# mkr1000.net
KiCad netlist of a schematic drawn in EAGLE
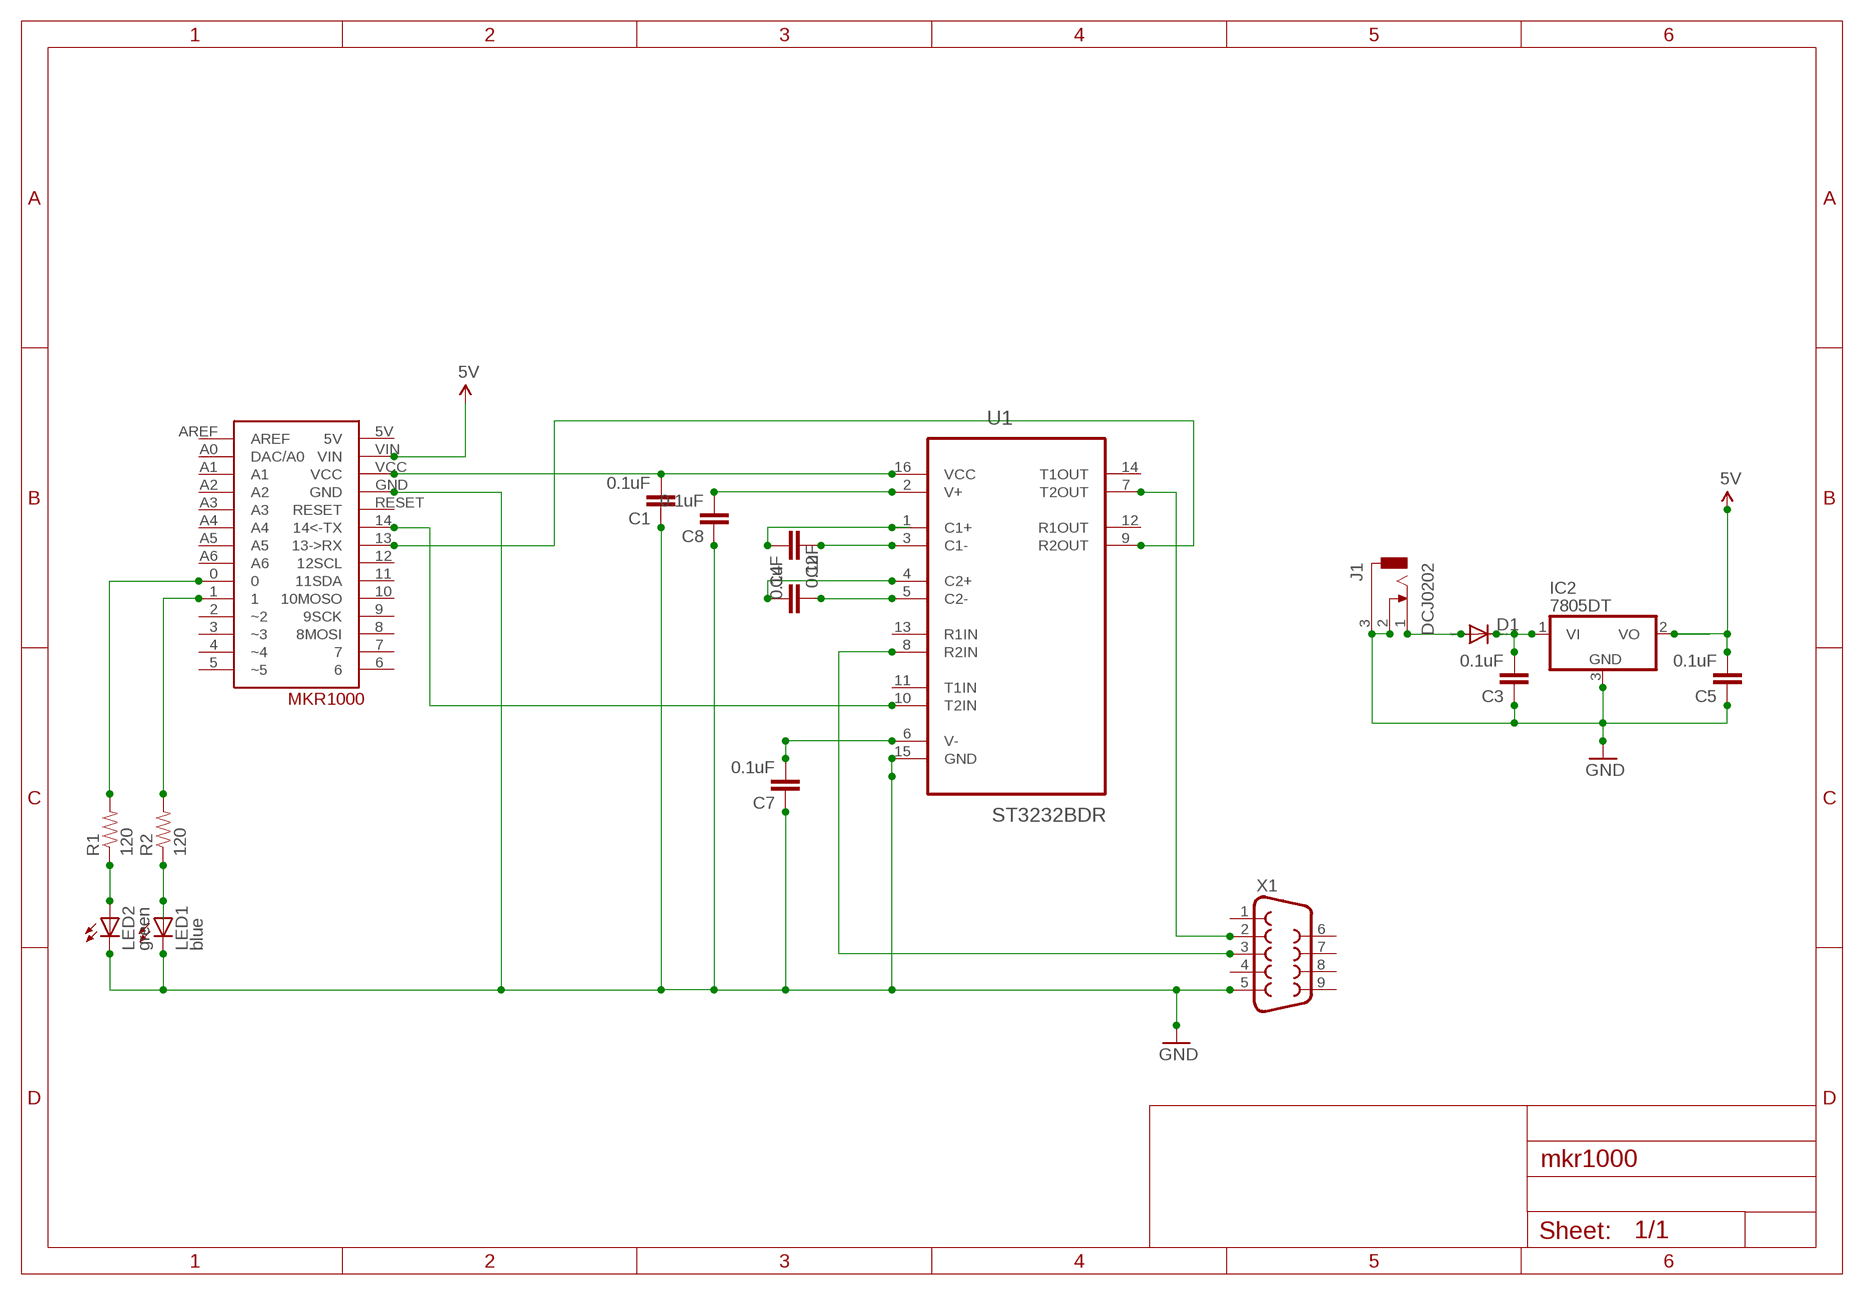
[diagram p0: schematic, sheet 1]

(export (version "E")
  (design (tool "Eeschema 10.0.6"))
  (components
    (comp (ref "C1")
      (value "0.1uF")
      (footprint "eagle-import:0603-CAP")
      (libsource (lib "eagle-import") (part "0.1UF-25V(+80/-20%)(0603)"))
    )
    (comp (ref "C2")
      (value "0.1uF")
      (footprint "eagle-import:0603-CAP")
      (libsource (lib "eagle-import") (part "0.1UF-25V(+80/-20%)(0603)"))
    )
    (comp (ref "C3")
      (value "0.1uF")
      (footprint "eagle-import:0603-CAP")
      (libsource (lib "eagle-import") (part "0.1UF-25V(+80/-20%)(0603)"))
    )
    (comp (ref "C4")
      (value "0.1uF")
      (footprint "eagle-import:0603-CAP")
      (libsource (lib "eagle-import") (part "0.1UF-25V(+80/-20%)(0603)"))
    )
    (comp (ref "C5")
      (value "0.1uF")
      (footprint "eagle-import:0603-CAP")
      (libsource (lib "eagle-import") (part "0.1UF-25V(+80/-20%)(0603)"))
    )
    (comp (ref "C7")
      (value "0.1uF")
      (footprint "eagle-import:0603-CAP")
      (libsource (lib "eagle-import") (part "0.1UF-25V(+80/-20%)(0603)"))
    )
    (comp (ref "C8")
      (value "0.1uF")
      (footprint "eagle-import:0603-CAP")
      (libsource (lib "eagle-import") (part "0.1UF-25V(+80/-20%)(0603)"))
    )
    (comp (ref "D1")
      (value "DIODE-SMB")
      (footprint "eagle-import:SMB")
      (libsource (lib "eagle-import") (part "DIODE-SMB"))
    )
    (comp (ref "IC2")
      (value "7805DT")
      (footprint "eagle-import:TO252")
      (libsource (lib "eagle-import") (part "78DT05"))
    )
    (comp (ref "J1")
      (value "DCJ0202")
      (footprint "eagle-import:DCJ0202")
      (libsource (lib "eagle-import") (part "DCJ0202"))
    )
    (comp (ref "LED1")
      (value "blue")
      (footprint "eagle-import:SML0805")
      (libsource (lib "eagle-import") (part "LEDSML0805"))
    )
    (comp (ref "LED2")
      (value "green")
      (footprint "eagle-import:SML0805")
      (libsource (lib "eagle-import") (part "LEDSML0805"))
    )
    (comp (ref "MKR1000")
      (value "MKR1000")
      (footprint "eagle-import:MKR1000")
      (libsource (lib "eagle-import") (part "MKR1000"))
    )
    (comp (ref "R1")
      (value "120")
      (footprint "eagle-import:0805")
      (libsource (lib "eagle-import") (part "RESISTOR0805-RES"))
    )
    (comp (ref "R2")
      (value "120")
      (footprint "eagle-import:0805")
      (libsource (lib "eagle-import") (part "RESISTOR0805-RES"))
    )
    (comp (ref "U1")
      (value "ST3232BDR")
      (footprint "eagle-import:SOIC127P600X175-16N")
      (libsource (lib "eagle-import") (part "ST3232BDR"))
    )
    (comp (ref "X1")
      (value "DB9FEMALE")
      (footprint "eagle-import:DB9")
      (libsource (lib "eagle-import") (part "DB9FEMALE"))
    )
  )
  (nets
    (net (code "1") (name "5V") (class "Default")
      (node (ref "C5") (pin "2") (pinfunction "2_2") (pintype "passive"))
      (node (ref "IC2") (pin "2") (pinfunction "VO_2") (pintype "passive"))
      (node (ref "MKR1000") (pin "VIN") (pinfunction "VIN_VIN") (pintype "bidirectional"))
    )
    (net (code "2") (name "GND") (class "Default")
      (node (ref "C1") (pin "1") (pinfunction "1_1") (pintype "passive"))
      (node (ref "C3") (pin "1") (pinfunction "1_1") (pintype "passive"))
      (node (ref "C5") (pin "1") (pinfunction "1_1") (pintype "passive"))
      (node (ref "C7") (pin "1") (pinfunction "1_1") (pintype "passive"))
      (node (ref "C8") (pin "1") (pinfunction "1_1") (pintype "passive"))
      (node (ref "IC2") (pin "3") (pinfunction "GND_3") (pintype "passive"))
      (node (ref "J1") (pin "2") (pinfunction "2_2") (pintype "passive"))
      (node (ref "J1") (pin "3") (pinfunction "1_3") (pintype "passive"))
      (node (ref "LED1") (pin "C") (pinfunction "C_C") (pintype "passive"))
      (node (ref "LED2") (pin "C") (pinfunction "C_C") (pintype "passive"))
      (node (ref "MKR1000") (pin "GND") (pinfunction "GND_GND") (pintype "bidirectional"))
      (node (ref "U1") (pin "15") (pinfunction "GND_15") (pintype "passive"))
      (node (ref "X1") (pin "5") (pinfunction "5_5") (pintype "passive"))
    )
    (net (code "3") (name "Net-(IC2-VI)") (class "Default")
      (node (ref "C3") (pin "2") (pinfunction "2_2") (pintype "passive"))
      (node (ref "D1") (pin "C") (pinfunction "C_C") (pintype "passive"))
      (node (ref "IC2") (pin "1") (pinfunction "VI_1") (pintype "input"))
    )
    (net (code "4") (name "Net-(J1-3)") (class "Default")
      (node (ref "D1") (pin "A") (pinfunction "A_A") (pintype "passive"))
      (node (ref "J1") (pin "1") (pinfunction "3_1") (pintype "passive"))
    )
    (net (code "5") (name "Net-(LED1-PadA)") (class "Default")
      (node (ref "LED1") (pin "A") (pinfunction "A_A") (pintype "passive"))
      (node (ref "R2") (pin "1") (pinfunction "1_1") (pintype "passive"))
    )
    (net (code "6") (name "Net-(LED2-PadA)") (class "Default")
      (node (ref "LED2") (pin "A") (pinfunction "A_A") (pintype "passive"))
      (node (ref "R1") (pin "1") (pinfunction "1_1") (pintype "passive"))
    )
    (net (code "7") (name "Net-(MKR1000-13->RX)") (class "Default")
      (node (ref "MKR1000") (pin "13") (pinfunction "13->RX_13") (pintype "bidirectional"))
      (node (ref "U1") (pin "9") (pinfunction "R2OUT_9") (pintype "output"))
    )
    (net (code "8") (name "Net-(MKR1000-14<-TX)") (class "Default")
      (node (ref "MKR1000") (pin "14") (pinfunction "14<-TX_14") (pintype "bidirectional"))
      (node (ref "U1") (pin "10") (pinfunction "T2IN_10") (pintype "input"))
    )
    (net (code "9") (name "Net-(MKR1000-Pad0)") (class "Default")
      (node (ref "MKR1000") (pin "0") (pinfunction "0_0") (pintype "bidirectional"))
      (node (ref "R1") (pin "2") (pinfunction "2_2") (pintype "passive"))
    )
    (net (code "10") (name "Net-(MKR1000-Pad1)") (class "Default")
      (node (ref "MKR1000") (pin "1") (pinfunction "1_1") (pintype "bidirectional"))
      (node (ref "R2") (pin "2") (pinfunction "2_2") (pintype "passive"))
    )
    (net (code "11") (name "Net-(U1-C1+)") (class "Default")
      (node (ref "C2") (pin "2") (pinfunction "2_2") (pintype "passive"))
      (node (ref "U1") (pin "1") (pinfunction "C1+_1") (pintype "passive"))
    )
    (net (code "12") (name "Net-(U1-C1-)") (class "Default")
      (node (ref "C2") (pin "1") (pinfunction "1_1") (pintype "passive"))
      (node (ref "U1") (pin "3") (pinfunction "C1-_3") (pintype "passive"))
    )
    (net (code "13") (name "Net-(U1-C2+)") (class "Default")
      (node (ref "C4") (pin "1") (pinfunction "1_1") (pintype "passive"))
      (node (ref "U1") (pin "4") (pinfunction "C2+_4") (pintype "passive"))
    )
    (net (code "14") (name "Net-(U1-C2-)") (class "Default")
      (node (ref "C4") (pin "2") (pinfunction "2_2") (pintype "passive"))
      (node (ref "U1") (pin "5") (pinfunction "C2-_5") (pintype "passive"))
    )
    (net (code "15") (name "Net-(U1-R2IN)") (class "Default")
      (node (ref "U1") (pin "8") (pinfunction "R2IN_8") (pintype "input"))
      (node (ref "X1") (pin "3") (pinfunction "3_3") (pintype "passive"))
    )
    (net (code "16") (name "Net-(U1-T2OUT)") (class "Default")
      (node (ref "U1") (pin "7") (pinfunction "T2OUT_7") (pintype "output"))
      (node (ref "X1") (pin "2") (pinfunction "2_2") (pintype "passive"))
    )
    (net (code "17") (name "Net-(U1-V+)") (class "Default")
      (node (ref "C8") (pin "2") (pinfunction "2_2") (pintype "passive"))
      (node (ref "U1") (pin "2") (pinfunction "V+_2") (pintype "power_in"))
    )
    (net (code "18") (name "Net-(U1-V-)") (class "Default")
      (node (ref "C7") (pin "2") (pinfunction "2_2") (pintype "passive"))
      (node (ref "U1") (pin "6") (pinfunction "V-_6") (pintype "power_in"))
    )
    (net (code "19") (name "Net-(U1-VCC)") (class "Default")
      (node (ref "C1") (pin "2") (pinfunction "2_2") (pintype "passive"))
      (node (ref "MKR1000") (pin "VCC") (pinfunction "VCC_VCC") (pintype "bidirectional"))
      (node (ref "U1") (pin "16") (pinfunction "VCC_16") (pintype "power_in"))
    )
    (net (code "20") (name "unconnected-(MKR1000-8MOSI-Pad8)") (class "Default")
      (node (ref "MKR1000") (pin "8") (pinfunction "8MOSI_8") (pintype "bidirectional"))
    )
    (net (code "21") (name "unconnected-(MKR1000-9SCK-Pad9)") (class "Default")
      (node (ref "MKR1000") (pin "9") (pinfunction "9SCK_9") (pintype "bidirectional"))
    )
    (net (code "22") (name "unconnected-(MKR1000-10MOSO-Pad10)") (class "Default")
      (node (ref "MKR1000") (pin "10") (pinfunction "10MOSO_10") (pintype "bidirectional"))
    )
    (net (code "23") (name "unconnected-(MKR1000-11SDA-Pad11)") (class "Default")
      (node (ref "MKR1000") (pin "11") (pinfunction "11SDA_11") (pintype "bidirectional"))
    )
    (net (code "24") (name "unconnected-(MKR1000-12SCL-Pad12)") (class "Default")
      (node (ref "MKR1000") (pin "12") (pinfunction "12SCL_12") (pintype "bidirectional"))
    )
    (net (code "25") (name "unconnected-(MKR1000-DAC{slash}A0-PadA0)") (class "Default")
      (node (ref "MKR1000") (pin "A0") (pinfunction "DAC/A0_A0") (pintype "bidirectional"))
    )
    (net (code "26") (name "unconnected-(MKR1000-Pad5V)") (class "Default")
      (node (ref "MKR1000") (pin "5V") (pinfunction "5V_5V") (pintype "bidirectional"))
    )
    (net (code "27") (name "unconnected-(MKR1000-Pad6)") (class "Default")
      (node (ref "MKR1000") (pin "6") (pinfunction "6_6") (pintype "bidirectional"))
    )
    (net (code "28") (name "unconnected-(MKR1000-Pad7)") (class "Default")
      (node (ref "MKR1000") (pin "7") (pinfunction "7_7") (pintype "bidirectional"))
    )
    (net (code "29") (name "unconnected-(MKR1000-PadA1)") (class "Default")
      (node (ref "MKR1000") (pin "A1") (pinfunction "A1_A1") (pintype "bidirectional"))
    )
    (net (code "30") (name "unconnected-(MKR1000-PadA2)") (class "Default")
      (node (ref "MKR1000") (pin "A2") (pinfunction "A2_A2") (pintype "bidirectional"))
    )
    (net (code "31") (name "unconnected-(MKR1000-PadA3)") (class "Default")
      (node (ref "MKR1000") (pin "A3") (pinfunction "A3_A3") (pintype "bidirectional"))
    )
    (net (code "32") (name "unconnected-(MKR1000-PadA4)") (class "Default")
      (node (ref "MKR1000") (pin "A4") (pinfunction "A4_A4") (pintype "bidirectional"))
    )
    (net (code "33") (name "unconnected-(MKR1000-PadA5)") (class "Default")
      (node (ref "MKR1000") (pin "A5") (pinfunction "A5_A5") (pintype "bidirectional"))
    )
    (net (code "34") (name "unconnected-(MKR1000-PadA6)") (class "Default")
      (node (ref "MKR1000") (pin "A6") (pinfunction "A6_A6") (pintype "bidirectional"))
    )
    (net (code "35") (name "unconnected-(MKR1000-PadAREF)") (class "Default")
      (node (ref "MKR1000") (pin "AREF") (pinfunction "AREF_AREF") (pintype "bidirectional"))
    )
    (net (code "36") (name "unconnected-(MKR1000-PadRESET)") (class "Default")
      (node (ref "MKR1000") (pin "RESET") (pinfunction "RESET_RESET") (pintype "bidirectional"))
    )
    (net (code "37") (name "unconnected-(MKR1000-~{2}-Pad2)") (class "Default")
      (node (ref "MKR1000") (pin "2") (pinfunction "~{2}_2") (pintype "bidirectional"))
    )
    (net (code "38") (name "unconnected-(MKR1000-~{3}-Pad3)") (class "Default")
      (node (ref "MKR1000") (pin "3") (pinfunction "~{3}_3") (pintype "bidirectional"))
    )
    (net (code "39") (name "unconnected-(MKR1000-~{4}-Pad4)") (class "Default")
      (node (ref "MKR1000") (pin "4") (pinfunction "~{4}_4") (pintype "bidirectional"))
    )
    (net (code "40") (name "unconnected-(MKR1000-~{5}-Pad5)") (class "Default")
      (node (ref "MKR1000") (pin "5") (pinfunction "~{5}_5") (pintype "bidirectional"))
    )
    (net (code "41") (name "unconnected-(U1-R1IN-Pad13)") (class "Default")
      (node (ref "U1") (pin "13") (pinfunction "R1IN_13") (pintype "input"))
    )
    (net (code "42") (name "unconnected-(U1-R1OUT-Pad12)") (class "Default")
      (node (ref "U1") (pin "12") (pinfunction "R1OUT_12") (pintype "output"))
    )
    (net (code "43") (name "unconnected-(U1-T1IN-Pad11)") (class "Default")
      (node (ref "U1") (pin "11") (pinfunction "T1IN_11") (pintype "input"))
    )
    (net (code "44") (name "unconnected-(U1-T1OUT-Pad14)") (class "Default")
      (node (ref "U1") (pin "14") (pinfunction "T1OUT_14") (pintype "output"))
    )
    (net (code "45") (name "unconnected-(X1-Pad1)") (class "Default")
      (node (ref "X1") (pin "1") (pinfunction "1_1") (pintype "passive"))
    )
    (net (code "46") (name "unconnected-(X1-Pad4)") (class "Default")
      (node (ref "X1") (pin "4") (pinfunction "4_4") (pintype "passive"))
    )
    (net (code "47") (name "unconnected-(X1-Pad6)") (class "Default")
      (node (ref "X1") (pin "6") (pinfunction "6_6") (pintype "passive"))
    )
    (net (code "48") (name "unconnected-(X1-Pad7)") (class "Default")
      (node (ref "X1") (pin "7") (pinfunction "7_7") (pintype "passive"))
    )
    (net (code "49") (name "unconnected-(X1-Pad8)") (class "Default")
      (node (ref "X1") (pin "8") (pinfunction "8_8") (pintype "passive"))
    )
    (net (code "50") (name "unconnected-(X1-Pad9)") (class "Default")
      (node (ref "X1") (pin "9") (pinfunction "9_9") (pintype "passive"))
    )
  )
)
